# HIVE_SIGHT_WROOM.net
KiCad netlist of a schematic drawn in Altium Designer
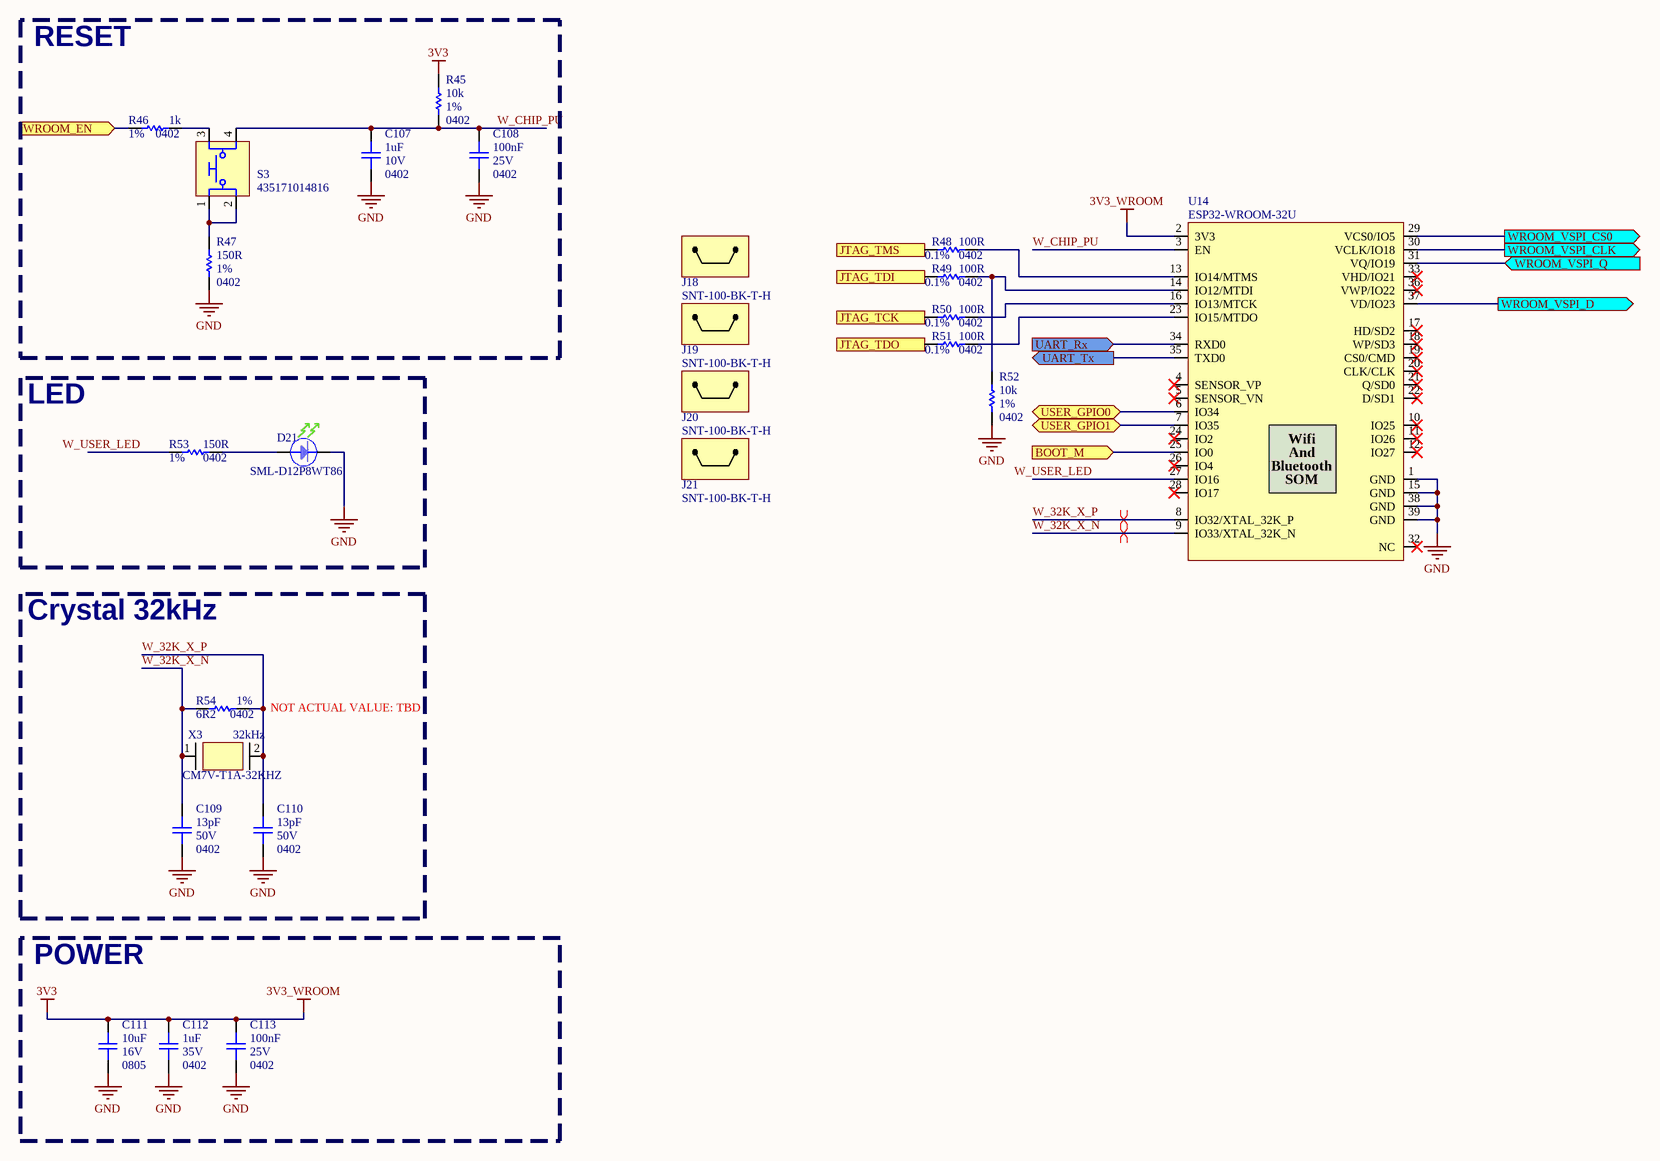
[diagram p0: HIVE_SIGHT_WROOM.SchDoc]

(export (version "E")
  (design (tool "Eeschema 10.0.6"))
  (components
    (comp (ref "C107")
      (value "1uF")
      (footprint "CAP_CER_0402")
      (description "CAP - CER 1uF 20% 10V X5R - 0402")
      (fields
        (field (name "TOLERANCE") "20%")
        (field (name "PACKAGE") "0402")
        (field (name "VOLTAGE RATING") "10V")
        (field (name "Comment") "CL05A105MP5NNNC")
        (field (name "CREATEDBY/DATE") "Jonathan Bouchard 2018-07-05")
        (field (name "VERIFIEDBY") "Arnaud Samson 16-07-18")
      )
      (libsource (lib "GRAMS_MASTER_LIB") (part "CAP_CER_CL05A105MP5NNNC"))
    )
    (comp (ref "C108")
      (value "100nF")
      (footprint "GRAMS_MASTER_LIB_PCB:CAP_CER_0402")
      (description "CAP - CER 0.1uF 10% 25V X5R - 0402")
      (fields
        (field (name "TOLERANCE") "10%")
        (field (name "PACKAGE") "0402")
        (field (name "VOLTAGE RATING") "25V")
        (field (name "Comment") "CL05A104KA5NNNC")
        (field (name "CREATEDBY/DATE") "Keven Deslandes - 2018/09/26")
        (field (name "VERIFIEDBY") "Nicolas Roy - 2018/12/11")
      )
      (libsource (lib "GRAMS_MASTER_LIB_SCH") (part "CAP_CER_CL05A104KA5NNNC"))
    )
    (comp (ref "C109")
      (value "13pF")
      (footprint "CAP_CER_0402")
      (description "CAP - CER 13PF 50V C0G/NP0 - 0402")
      (fields
        (field (name "TOLERANCE") "±5%")
        (field (name "PACKAGE") "0402")
        (field (name "VOLTAGE RATING") "50V")
        (field (name "Comment") "CC0402JRNPO9BN130")
        (field (name "CREATEDBY/DATE") "Hubert Dube - 04/10/20")
        (field (name "VERIFIEDBY") "Louis-Daniel Gaulin - 09/11/2020")
      )
      (libsource (lib "SWARMUS_LIB") (part "CAP_CER_CC0402JRNPO9BN130"))
    )
    (comp (ref "C110")
      (value "13pF")
      (footprint "CAP_CER_0402")
      (description "CAP - CER 13PF 50V C0G/NP0 - 0402")
      (fields
        (field (name "TOLERANCE") "±5%")
        (field (name "PACKAGE") "0402")
        (field (name "VOLTAGE RATING") "50V")
        (field (name "Comment") "CC0402JRNPO9BN130")
        (field (name "CREATEDBY/DATE") "Hubert Dube - 04/10/20")
        (field (name "VERIFIEDBY") "Louis-Daniel Gaulin - 09/11/2020")
      )
      (libsource (lib "SWARMUS_LIB") (part "CAP_CER_CC0402JRNPO9BN130"))
    )
    (comp (ref "C111")
      (value "10uF")
      (footprint "CAP_CER_0805")
      (description "CAP - CER 10UF 16V X5R - 0805")
      (fields
        (field (name "TOLERANCE") "10%")
        (field (name "PACKAGE") "0805")
        (field (name "VOLTAGE RATING") "16V")
        (field (name "Comment") "0805YD106KAT2A")
        (field (name "CREATEDBY/DATE") "L-P Gauthier / 2018-05-29")
        (field (name "VERIFIEDBY") "Caroline Paulin - 27 sept 2018")
      )
      (libsource (lib "GRAMS_MASTER_LIB") (part "CAP_CER_0805YD106KAT2A"))
    )
    (comp (ref "C112")
      (value "1uF")
      (footprint "GRAMS_MASTER_LIB_PCB:CAP_CER_0402")
      (description "CAP - CER 1uF 10% 35V X5R - 0402")
      (fields
        (field (name "TOLERANCE") "10%")
        (field (name "PACKAGE") "0402")
        (field (name "VOLTAGE RATING") "35V")
        (field (name "Comment") "CL05A105KL5NRNC")
        (field (name "CREATEDBY/DATE") "Nicolas Roy 2018-10-03")
        (field (name "VERIFIEDBY") "Caroline Paulin - 18 janv 2019")
      )
      (libsource (lib "GRAMS_MASTER_LIB_SCH") (part "CAP_CER_CL05A105KL5NRNC"))
    )
    (comp (ref "C113")
      (value "100nF")
      (footprint "GRAMS_MASTER_LIB_PCB:CAP_CER_0402")
      (description "CAP - CER 0.1uF 10% 25V X5R - 0402")
      (fields
        (field (name "TOLERANCE") "10%")
        (field (name "PACKAGE") "0402")
        (field (name "VOLTAGE RATING") "25V")
        (field (name "Comment") "CL05A104KA5NNNC")
        (field (name "CREATEDBY/DATE") "Keven Deslandes - 2018/09/26")
        (field (name "VERIFIEDBY") "Nicolas Roy - 2018/12/11")
      )
      (libsource (lib "GRAMS_MASTER_LIB_SCH") (part "CAP_CER_CL05A104KA5NNNC"))
    )
    (comp (ref "D21")
      (value "SML-D12P8WT86")
      (footprint "GRAMS_MASTER_LIB_PCB:LED_SML-D12P8WT86")
      (description "LED - GREEN DIFFUSED 0603 SMD - 0603")
      (fields
        (field (name "CREATEDBY/DATE") "Keven Deslandes - 2018/11/21")
        (field (name "VERIFIEDBY") "Caroline Paulin - 13 février 2019")
      )
      (libsource (lib "GRAMS_MASTER_LIB_SCH") (part "LED_SML-D12P8WT86"))
    )
    (comp (ref "J18")
      (value "SNT-100-BK-T-H")
      (footprint "CON_JMP_SNT-100-BK-T-H")
      (description "CON - CONN SHUNT - MEC")
      (fields
        (field (name "CREATEDBY/DATE") "Arnaud Samson - 09/07/18")
        (field (name "VERIFIEDBY") "Jonathan Bouchard 2018-07-12")
      )
      (libsource (lib "GRAMS_MASTER_LIB") (part "CON_JMP_SNT-100-BK-T-H"))
    )
    (comp (ref "J19")
      (value "SNT-100-BK-T-H")
      (footprint "CON_JMP_SNT-100-BK-T-H")
      (description "CON - CONN SHUNT - MEC")
      (fields
        (field (name "CREATEDBY/DATE") "Arnaud Samson - 09/07/18")
        (field (name "VERIFIEDBY") "Jonathan Bouchard 2018-07-12")
      )
      (libsource (lib "GRAMS_MASTER_LIB") (part "CON_JMP_SNT-100-BK-T-H"))
    )
    (comp (ref "J20")
      (value "SNT-100-BK-T-H")
      (footprint "CON_JMP_SNT-100-BK-T-H")
      (description "CON - CONN SHUNT - MEC")
      (fields
        (field (name "CREATEDBY/DATE") "Arnaud Samson - 09/07/18")
        (field (name "VERIFIEDBY") "Jonathan Bouchard 2018-07-12")
      )
      (libsource (lib "GRAMS_MASTER_LIB") (part "CON_JMP_SNT-100-BK-T-H"))
    )
    (comp (ref "J21")
      (value "SNT-100-BK-T-H")
      (footprint "CON_JMP_SNT-100-BK-T-H")
      (description "CON - CONN SHUNT - MEC")
      (fields
        (field (name "CREATEDBY/DATE") "Arnaud Samson - 09/07/18")
        (field (name "VERIFIEDBY") "Jonathan Bouchard 2018-07-12")
      )
      (libsource (lib "GRAMS_MASTER_LIB") (part "CON_JMP_SNT-100-BK-T-H"))
    )
    (comp (ref "R45")
      (value "10k")
      (footprint "GRAMS_MASTER_LIB_PCB:RES_0402")
      (description "RES - 10K OHMS 1% 1/16W - 0402")
      (fields
        (field (name "TOLERANCE") "1%")
        (field (name "PACKAGE") "0402")
        (field (name "Comment") "RC0402FR-0710KL")
        (field (name "CREATEDBY/DATE") "Nicolas V. (2018-11-20)")
        (field (name "VERIFIEDBY") "Nicolas V. (2018-11-20)")
      )
      (libsource (lib "GRAMS_MASTER_LIB_SCH") (part "RES_RC0402FR-0710KL"))
    )
    (comp (ref "R46")
      (value "1k")
      (footprint "GRAMS_MASTER_LIB_PCB:RES_0402")
      (description "RES - 1K OHM 1% 1/16W - 0402")
      (fields
        (field (name "TOLERANCE") "1%")
        (field (name "PACKAGE") "0402")
        (field (name "Comment") "RC0402FR-071KL")
        (field (name "CREATEDBY/DATE") "Jonathan Bouchard 2018-07-05")
        (field (name "VERIFIEDBY") "Arnaud Samson 16-07-18")
      )
      (libsource (lib "GRAMS_MASTER_LIB_SCH") (part "RES_RC0402FR-071KL"))
    )
    (comp (ref "R47")
      (value "150R")
      (footprint "RES_0402")
      (description "RES - 150R 1% 1/16W - 0402")
      (fields
        (field (name "TOLERANCE") "1%")
        (field (name "PACKAGE") "0402")
        (field (name "Comment") "RC0402FR-07150RL")
        (field (name "CREATEDBY/DATE") "Jonathan Bouchard 2019-03-25")
        (field (name "VERIFIEDBY") "Nicolas V. (2019-05-02)")
      )
      (libsource (lib "GRAMS_MASTER_LIB") (part "RES_RC0402FR-07150RL"))
    )
    (comp (ref "R48")
      (value "100R")
      (footprint "RES_0402")
      (description "RES - 100 OHM 0.1% 1/20W NON-MAG - 0402")
      (fields
        (field (name "TOLERANCE") "0.1%")
        (field (name "PACKAGE") "0402")
        (field (name "Comment") "PNM0402E1000BST1")
        (field (name "CREATEDBY/DATE") "Jonathan Bouchard 2018-04-3")
        (field (name "VERIFIEDBY") "Arnaud Samson 17-07-18")
      )
      (libsource (lib "GRAMS_MASTER_LIB") (part "RES_NOMAG_PNM0402E1000BST1"))
    )
    (comp (ref "R49")
      (value "100R")
      (footprint "RES_0402")
      (description "RES - 100 OHM 0.1% 1/20W NON-MAG - 0402")
      (fields
        (field (name "TOLERANCE") "0.1%")
        (field (name "PACKAGE") "0402")
        (field (name "Comment") "PNM0402E1000BST1")
        (field (name "CREATEDBY/DATE") "Jonathan Bouchard 2018-04-3")
        (field (name "VERIFIEDBY") "Arnaud Samson 17-07-18")
      )
      (libsource (lib "GRAMS_MASTER_LIB") (part "RES_NOMAG_PNM0402E1000BST1"))
    )
    (comp (ref "R50")
      (value "100R")
      (footprint "RES_0402")
      (description "RES - 100 OHM 0.1% 1/20W NON-MAG - 0402")
      (fields
        (field (name "TOLERANCE") "0.1%")
        (field (name "PACKAGE") "0402")
        (field (name "Comment") "PNM0402E1000BST1")
        (field (name "CREATEDBY/DATE") "Jonathan Bouchard 2018-04-3")
        (field (name "VERIFIEDBY") "Arnaud Samson 17-07-18")
      )
      (libsource (lib "GRAMS_MASTER_LIB") (part "RES_NOMAG_PNM0402E1000BST1"))
    )
    (comp (ref "R51")
      (value "100R")
      (footprint "RES_0402")
      (description "RES - 100 OHM 0.1% 1/20W NON-MAG - 0402")
      (fields
        (field (name "TOLERANCE") "0.1%")
        (field (name "PACKAGE") "0402")
        (field (name "Comment") "PNM0402E1000BST1")
        (field (name "CREATEDBY/DATE") "Jonathan Bouchard 2018-04-3")
        (field (name "VERIFIEDBY") "Arnaud Samson 17-07-18")
      )
      (libsource (lib "GRAMS_MASTER_LIB") (part "RES_NOMAG_PNM0402E1000BST1"))
    )
    (comp (ref "R52")
      (value "10k")
      (footprint "GRAMS_MASTER_LIB_PCB:RES_0402")
      (description "RES - 10K OHMS 1% 1/16W - 0402")
      (fields
        (field (name "TOLERANCE") "1%")
        (field (name "PACKAGE") "0402")
        (field (name "Comment") "RC0402FR-0710KL")
        (field (name "CREATEDBY/DATE") "Nicolas V. (2018-11-20)")
        (field (name "VERIFIEDBY") "Nicolas V. (2018-11-20)")
      )
      (libsource (lib "GRAMS_MASTER_LIB_SCH") (part "RES_RC0402FR-0710KL"))
    )
    (comp (ref "R53")
      (value "150R")
      (footprint "RES_0402")
      (description "RES - 150R 1% 1/16W - 0402")
      (fields
        (field (name "TOLERANCE") "1%")
        (field (name "PACKAGE") "0402")
        (field (name "Comment") "RC0402FR-07150RL")
        (field (name "CREATEDBY/DATE") "Jonathan Bouchard 2019-03-25")
        (field (name "VERIFIEDBY") "Nicolas V. (2019-05-02)")
      )
      (libsource (lib "GRAMS_MASTER_LIB") (part "RES_RC0402FR-07150RL"))
    )
    (comp (ref "R54")
      (value "6R2")
      (footprint "RES_0402")
      (description "RES - 6.2R 1% 1/16W - 0402")
      (fields
        (field (name "TOLERANCE") "1%")
        (field (name "PACKAGE") "0402")
        (field (name "Comment") "RC0402FR-076R2L")
        (field (name "CREATEDBY/DATE") "Hubert Dubé 04/10/2020")
        (field (name "VERIFIEDBY") "Louis-Daniel Gaulin - 09/11/2020")
      )
      (libsource (lib "SWARMUS_LIB") (part "RES_RC0402FR-076R2L"))
    )
    (comp (ref "S3")
      (value "435171014816")
      (footprint "SWI_TACT_435171014816")
      (description "SWI - SWITCH TACTILE SPST-NO 0.05A 12V -SMD")
      (fields
        (field (name "CREATEDBY/DATE") "Hubert Dube - 22/07/20")
        (field (name "VERIFIEDBY") "Louis-Daniel Gaulin / 12-11-2020")
      )
      (libsource (lib "SWARMUS_LIB") (part "SWI_TACT_435171014816"))
    )
    (comp (ref "U14")
      (value "ESP32-WROOM-32U")
      (footprint "COM_ESP32-WROOM-32U(8MB)")
      (description "Bluetooth, WiFi 802.11b/g/n, Bluetooth v4.2  2.4GHz ~ 2.5GHz U.FL Surface Mount")
      (fields
        (field (name "VERIFIEDBY") "Philippe Arsenault - 15/12/2020")
        (field (name "CREATEDBY/DATE") "Hubert Dube -  12/12/20")
      )
      (libsource (lib "SWARMUS_LIB") (part "COM_ESP32-WROOM-32U(8MB)"))
    )
    (comp (ref "X3")
      (value "CM7V-T1A-32KHZ")
      (footprint "CRY_CM7V-T1A-32.768KHZ-12.5PF-20PPM-TA-QC")
      (description "CRY - 32.768KHZ tol:20ppm 12.5PF - 2-SMD")
      (fields
        (field (name "TOLERANCE") "±20ppm")
        (field (name "ALTIUM_VALUE") "32kHz")
        (field (name "CREATEDBY/DATE") "Hubert Dube - 21/07/20")
        (field (name "VERIFIEDBY") "Louis-Daniel Gaulin - 09/11/2020")
      )
      (libsource (lib "SWARMUS_LIB") (part "CRY_CM7V-T1A-32.768KHZ-12.5PF-20PPM-TA-QC"))
    )
  )
  (nets
    (net (code "1") (name "/BOOT_M") (class "Default")
      (node (ref "U14") (pin "25") (pinfunction "IO0_25") (pintype "passive"))
    )
    (net (code "2") (name "/JTAG_TCK") (class "Default")
      (node (ref "R50") (pin "2") (pinfunction "2_2") (pintype "passive"))
    )
    (net (code "3") (name "/JTAG_TDI") (class "Default")
      (node (ref "R49") (pin "2") (pinfunction "2_2") (pintype "passive"))
    )
    (net (code "4") (name "/JTAG_TDO") (class "Default")
      (node (ref "R51") (pin "2") (pinfunction "2_2") (pintype "passive"))
    )
    (net (code "5") (name "/JTAG_TMS") (class "Default")
      (node (ref "R48") (pin "2") (pinfunction "2_2") (pintype "passive"))
    )
    (net (code "6") (name "/UART_Rx") (class "Default")
      (node (ref "U14") (pin "34") (pinfunction "RXD0_34") (pintype "passive"))
    )
    (net (code "7") (name "/UART_Tx") (class "Default")
      (node (ref "U14") (pin "35") (pinfunction "TXD0_35") (pintype "passive"))
    )
    (net (code "8") (name "/USER_GPIO0") (class "Default")
      (node (ref "U14") (pin "6") (pinfunction "IO34_6") (pintype "passive"))
    )
    (net (code "9") (name "/USER_GPIO1") (class "Default")
      (node (ref "U14") (pin "7") (pinfunction "IO35_7") (pintype "passive"))
    )
    (net (code "10") (name "/WROOM_EN") (class "Default")
      (node (ref "R46") (pin "2") (pinfunction "2_2") (pintype "passive"))
    )
    (net (code "11") (name "/WROOM_VSPI_CLK") (class "Default")
      (node (ref "U14") (pin "30") (pinfunction "VCLK/IO18_30") (pintype "passive"))
    )
    (net (code "12") (name "/WROOM_VSPI_CS0") (class "Default")
      (node (ref "U14") (pin "29") (pinfunction "VCS0/IO5_29") (pintype "passive"))
    )
    (net (code "13") (name "/WROOM_VSPI_D") (class "Default")
      (node (ref "U14") (pin "37") (pinfunction "VD/IO23_37") (pintype "passive"))
    )
    (net (code "14") (name "/WROOM_VSPI_Q") (class "Default")
      (node (ref "U14") (pin "31") (pinfunction "VQ/IO19_31") (pintype "passive"))
    )
    (net (code "15") (name "/W_32K_X_N") (class "Default")
      (node (ref "C109") (pin "2") (pinfunction "2_2") (pintype "passive"))
      (node (ref "R54") (pin "2") (pinfunction "2_2") (pintype "passive"))
      (node (ref "U14") (pin "9") (pinfunction "IO33/XTAL_32K_N_9") (pintype "passive"))
      (node (ref "X3") (pin "1") (pinfunction "In/Out_1") (pintype "passive"))
    )
    (net (code "16") (name "/W_32K_X_P") (class "Default")
      (node (ref "C110") (pin "2") (pinfunction "2_2") (pintype "passive"))
      (node (ref "R54") (pin "1") (pinfunction "1_1") (pintype "passive"))
      (node (ref "U14") (pin "8") (pinfunction "IO32/XTAL_32K_P_8") (pintype "passive"))
      (node (ref "X3") (pin "2") (pinfunction "Out/In_2") (pintype "passive"))
    )
    (net (code "17") (name "/W_CHIP_PU") (class "Default")
      (node (ref "C107") (pin "2") (pinfunction "2_2") (pintype "passive"))
      (node (ref "C108") (pin "2") (pinfunction "2_2") (pintype "passive"))
      (node (ref "R45") (pin "1") (pinfunction "1_1") (pintype "passive"))
      (node (ref "S3") (pin "4") (pinfunction "4_4") (pintype "passive"))
      (node (ref "U14") (pin "3") (pinfunction "EN_3") (pintype "passive"))
    )
    (net (code "18") (name "/W_USER_LED") (class "Default")
      (node (ref "R53") (pin "2") (pinfunction "2_2") (pintype "passive"))
      (node (ref "U14") (pin "27") (pinfunction "IO16_27") (pintype "passive"))
    )
    (net (code "19") (name "3V3") (class "Default")
      (node (ref "C111") (pin "2") (pinfunction "2_2") (pintype "passive"))
      (node (ref "C112") (pin "2") (pinfunction "2_2") (pintype "passive"))
      (node (ref "C113") (pin "2") (pinfunction "2_2") (pintype "passive"))
      (node (ref "R45") (pin "2") (pinfunction "2_2") (pintype "passive"))
      (node (ref "U14") (pin "2") (pinfunction "3V3_2") (pintype "passive"))
    )
    (net (code "20") (name "GND") (class "Default")
      (node (ref "C107") (pin "1") (pinfunction "1_1") (pintype "passive"))
      (node (ref "C108") (pin "1") (pinfunction "1_1") (pintype "passive"))
      (node (ref "C109") (pin "1") (pinfunction "1_1") (pintype "passive"))
      (node (ref "C110") (pin "1") (pinfunction "1_1") (pintype "passive"))
      (node (ref "C111") (pin "1") (pinfunction "1_1") (pintype "passive"))
      (node (ref "C112") (pin "1") (pinfunction "1_1") (pintype "passive"))
      (node (ref "C113") (pin "1") (pinfunction "1_1") (pintype "passive"))
      (node (ref "D21") (pin "K") (pinfunction "K_K") (pintype "passive"))
      (node (ref "R47") (pin "1") (pinfunction "1_1") (pintype "passive"))
      (node (ref "R52") (pin "1") (pinfunction "1_1") (pintype "passive"))
      (node (ref "U14") (pin "1") (pinfunction "GND_1") (pintype "passive"))
      (node (ref "U14") (pin "15") (pinfunction "GND_15") (pintype "passive"))
      (node (ref "U14") (pin "38") (pinfunction "GND_38") (pintype "passive"))
      (node (ref "U14") (pin "39") (pinfunction "GND_39") (pintype "passive"))
    )
    (net (code "21") (name "Net-(D21-PadA)") (class "Default")
      (node (ref "D21") (pin "A") (pinfunction "A_A") (pintype "passive"))
      (node (ref "R53") (pin "1") (pinfunction "1_1") (pintype "passive"))
    )
    (net (code "22") (name "Net-(R46-Pad1)") (class "Default")
      (node (ref "R46") (pin "1") (pinfunction "1_1") (pintype "passive"))
      (node (ref "S3") (pin "3") (pinfunction "3_3") (pintype "passive"))
    )
    (net (code "23") (name "Net-(R47-Pad2)") (class "Default")
      (node (ref "R47") (pin "2") (pinfunction "2_2") (pintype "passive"))
      (node (ref "S3") (pin "1") (pinfunction "1_1") (pintype "passive"))
      (node (ref "S3") (pin "2") (pinfunction "2_2") (pintype "passive"))
    )
    (net (code "24") (name "Net-(U14-IO12{slash}MTDI)") (class "Default")
      (node (ref "R49") (pin "1") (pinfunction "1_1") (pintype "passive"))
      (node (ref "R52") (pin "2") (pinfunction "2_2") (pintype "passive"))
      (node (ref "U14") (pin "14") (pinfunction "IO12/MTDI_14") (pintype "passive"))
    )
    (net (code "25") (name "Net-(U14-IO13{slash}MTCK)") (class "Default")
      (node (ref "R50") (pin "1") (pinfunction "1_1") (pintype "passive"))
      (node (ref "U14") (pin "16") (pinfunction "IO13/MTCK_16") (pintype "passive"))
    )
    (net (code "26") (name "Net-(U14-IO14{slash}MTMS)") (class "Default")
      (node (ref "R48") (pin "1") (pinfunction "1_1") (pintype "passive"))
      (node (ref "U14") (pin "13") (pinfunction "IO14/MTMS_13") (pintype "passive"))
    )
    (net (code "27") (name "Net-(U14-IO15{slash}MTDO)") (class "Default")
      (node (ref "R51") (pin "1") (pinfunction "1_1") (pintype "passive"))
      (node (ref "U14") (pin "23") (pinfunction "IO15/MTDO_23") (pintype "passive"))
    )
    (net (code "28") (name "unconnected-(U14-CLK{slash}CLK-Pad20)") (class "Default")
      (node (ref "U14") (pin "20") (pinfunction "CLK/CLK_20") (pintype "passive+no_connect"))
    )
    (net (code "29") (name "unconnected-(U14-CS0{slash}CMD-Pad19)") (class "Default")
      (node (ref "U14") (pin "19") (pinfunction "CS0/CMD_19") (pintype "passive+no_connect"))
    )
    (net (code "30") (name "unconnected-(U14-D{slash}SD1-Pad22)") (class "Default")
      (node (ref "U14") (pin "22") (pinfunction "D/SD1_22") (pintype "passive+no_connect"))
    )
    (net (code "31") (name "unconnected-(U14-HD{slash}SD2-Pad17)") (class "Default")
      (node (ref "U14") (pin "17") (pinfunction "HD/SD2_17") (pintype "passive+no_connect"))
    )
    (net (code "32") (name "unconnected-(U14-IO2-Pad24)") (class "Default")
      (node (ref "U14") (pin "24") (pinfunction "IO2_24") (pintype "passive+no_connect"))
    )
    (net (code "33") (name "unconnected-(U14-IO4-Pad26)") (class "Default")
      (node (ref "U14") (pin "26") (pinfunction "IO4_26") (pintype "passive+no_connect"))
    )
    (net (code "34") (name "unconnected-(U14-IO17-Pad28)") (class "Default")
      (node (ref "U14") (pin "28") (pinfunction "IO17_28") (pintype "passive+no_connect"))
    )
    (net (code "35") (name "unconnected-(U14-IO25-Pad10)") (class "Default")
      (node (ref "U14") (pin "10") (pinfunction "IO25_10") (pintype "passive+no_connect"))
    )
    (net (code "36") (name "unconnected-(U14-IO26-Pad11)") (class "Default")
      (node (ref "U14") (pin "11") (pinfunction "IO26_11") (pintype "passive+no_connect"))
    )
    (net (code "37") (name "unconnected-(U14-IO27-Pad12)") (class "Default")
      (node (ref "U14") (pin "12") (pinfunction "IO27_12") (pintype "passive+no_connect"))
    )
    (net (code "38") (name "unconnected-(U14-NC-Pad32)") (class "Default")
      (node (ref "U14") (pin "32") (pinfunction "NC_32") (pintype "passive+no_connect"))
    )
    (net (code "39") (name "unconnected-(U14-Q{slash}SD0-Pad21)") (class "Default")
      (node (ref "U14") (pin "21") (pinfunction "Q/SD0_21") (pintype "passive+no_connect"))
    )
    (net (code "40") (name "unconnected-(U14-SENSOR_VN-Pad5)") (class "Default")
      (node (ref "U14") (pin "5") (pinfunction "SENSOR_VN_5") (pintype "passive+no_connect"))
    )
    (net (code "41") (name "unconnected-(U14-SENSOR_VP-Pad4)") (class "Default")
      (node (ref "U14") (pin "4") (pinfunction "SENSOR_VP_4") (pintype "passive+no_connect"))
    )
    (net (code "42") (name "unconnected-(U14-VHD{slash}IO21-Pad33)") (class "Default")
      (node (ref "U14") (pin "33") (pinfunction "VHD/IO21_33") (pintype "passive+no_connect"))
    )
    (net (code "43") (name "unconnected-(U14-VWP{slash}IO22-Pad36)") (class "Default")
      (node (ref "U14") (pin "36") (pinfunction "VWP/IO22_36") (pintype "passive+no_connect"))
    )
    (net (code "44") (name "unconnected-(U14-WP{slash}SD3-Pad18)") (class "Default")
      (node (ref "U14") (pin "18") (pinfunction "WP/SD3_18") (pintype "passive+no_connect"))
    )
  )
)
